# frets-analog.net
KiCad netlist of a schematic drawn in EAGLE
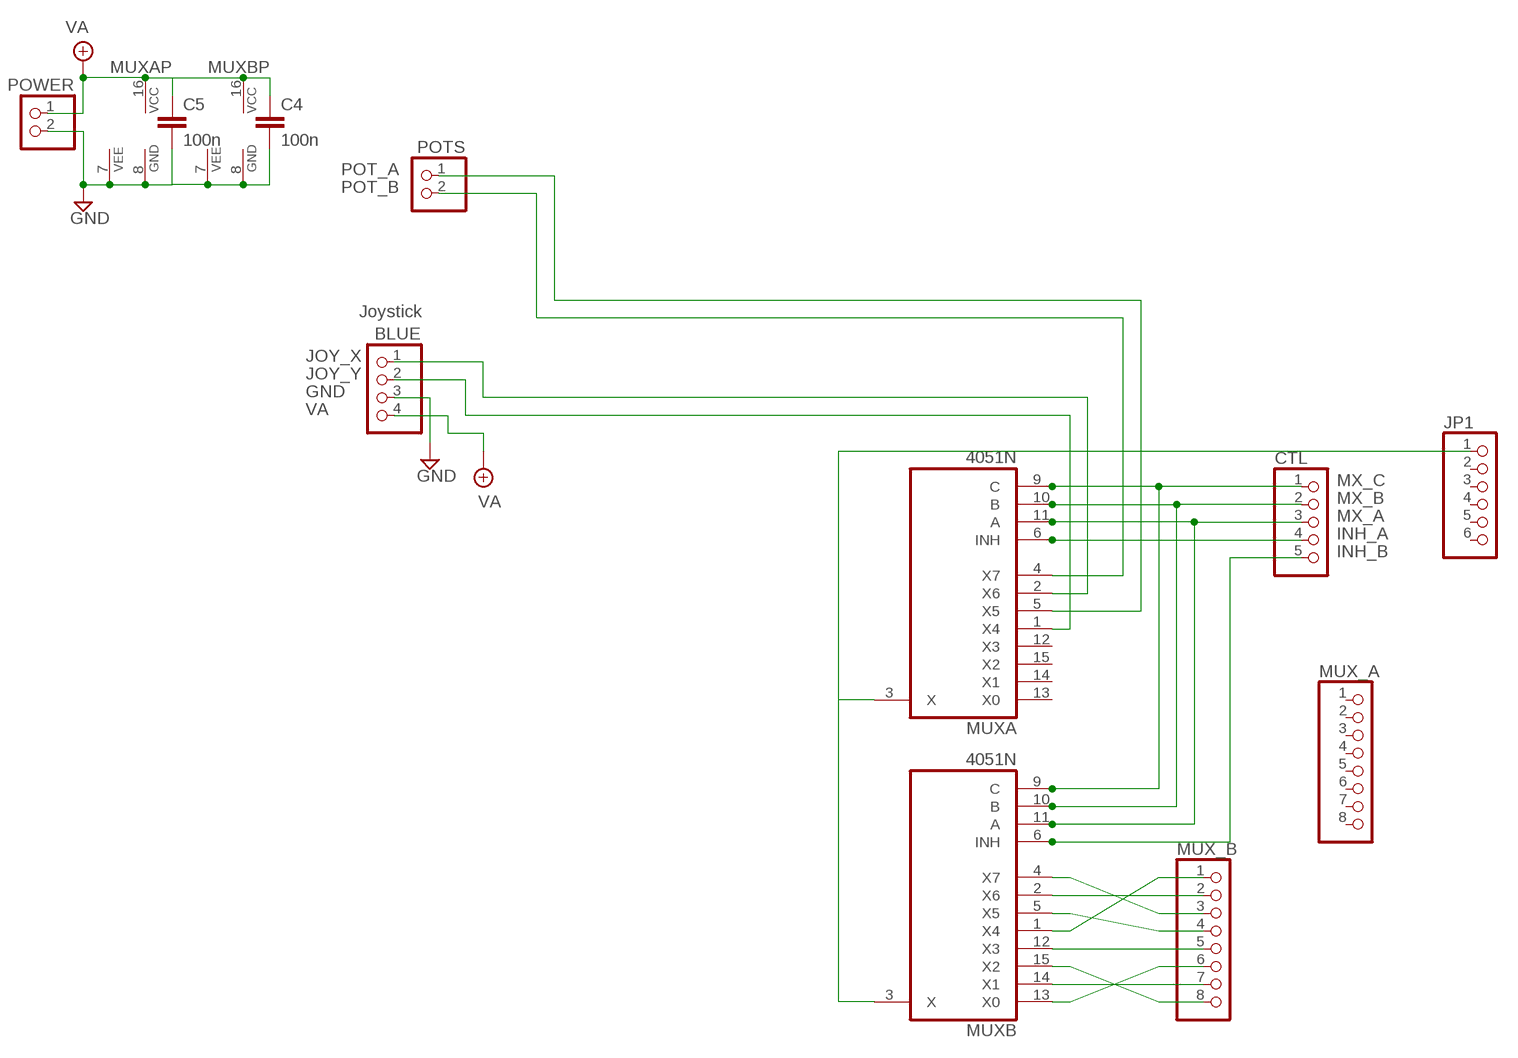
[diagram p0: schematic, sheet 1]

(export (version "E")
  (design (tool "Eeschema 10.0.6"))
  (components
    (comp (ref "BLUE")
      (value "PINHD-1X4")
      (footprint "eagle-import:1X04")
      (libsource (lib "eagle-import") (part "PINHD-1X4"))
    )
    (comp (ref "C4")
      (value "100n")
      (footprint "eagle-import:050X030_050_3")
      (libsource (lib "eagle-import") (part "050X030_050"))
    )
    (comp (ref "C5")
      (value "100n")
      (footprint "eagle-import:050X030_050_3")
      (libsource (lib "eagle-import") (part "050X030_050"))
    )
    (comp (ref "CTL")
      (value "PINHD-1X5")
      (footprint "eagle-import:1X05")
      (libsource (lib "eagle-import") (part "PINHD-1X5"))
    )
    (comp (ref "JP1")
      (value "PINHD-1X6")
      (footprint "eagle-import:1X06")
      (libsource (lib "eagle-import") (part "PINHD-1X6"))
    )
    (comp (ref "MUXA")
      (value "4051N")
      (footprint "eagle-import:DIL16")
      (libsource (lib "eagle-import") (part "4051N"))
    )
    (comp (ref "MUXB")
      (value "4051N")
      (footprint "eagle-import:DIL16")
      (libsource (lib "eagle-import") (part "4051N"))
    )
    (comp (ref "MUX_A")
      (value "PINHD-1X8")
      (footprint "eagle-import:1X08")
      (libsource (lib "eagle-import") (part "PINHD-1X8"))
    )
    (comp (ref "MUX_B")
      (value "PINHD-1X8")
      (footprint "eagle-import:1X08")
      (libsource (lib "eagle-import") (part "PINHD-1X8"))
    )
    (comp (ref "POTS")
      (value "PINHD-1X2")
      (footprint "eagle-import:1X02")
      (libsource (lib "eagle-import") (part "PINHD-1X2"))
    )
    (comp (ref "POWER")
      (value "PINHD-1X2")
      (footprint "eagle-import:1X02")
      (libsource (lib "eagle-import") (part "PINHD-1X2"))
    )
  )
  (nets
    (net (code "1") (name "/INH_A") (class "Default")
      (node (ref "CTL") (pin "4") (pinfunction "4_4") (pintype "passive"))
      (node (ref "MUXA") (pin "6") (pinfunction "INH_6") (pintype "input"))
    )
    (net (code "2") (name "/INH_B") (class "Default")
      (node (ref "CTL") (pin "5") (pinfunction "5_5") (pintype "passive"))
      (node (ref "MUXB") (pin "6") (pinfunction "INH_6") (pintype "input"))
    )
    (net (code "3") (name "/JOY_X") (class "Default")
      (node (ref "BLUE") (pin "1") (pinfunction "1_1") (pintype "passive"))
      (node (ref "MUXA") (pin "2") (pinfunction "X6_2") (pintype "bidirectional"))
    )
    (net (code "4") (name "/JOY_Y") (class "Default")
      (node (ref "BLUE") (pin "2") (pinfunction "2_2") (pintype "passive"))
      (node (ref "MUXA") (pin "1") (pinfunction "X4_1") (pintype "bidirectional"))
    )
    (net (code "5") (name "/MX_A") (class "Default")
      (node (ref "CTL") (pin "3") (pinfunction "3_3") (pintype "passive"))
      (node (ref "MUXA") (pin "11") (pinfunction "A_11") (pintype "input"))
      (node (ref "MUXB") (pin "11") (pinfunction "A_11") (pintype "input"))
    )
    (net (code "6") (name "/MX_B") (class "Default")
      (node (ref "CTL") (pin "2") (pinfunction "2_2") (pintype "passive"))
      (node (ref "MUXA") (pin "10") (pinfunction "B_10") (pintype "input"))
      (node (ref "MUXB") (pin "10") (pinfunction "B_10") (pintype "input"))
    )
    (net (code "7") (name "/MX_C") (class "Default")
      (node (ref "CTL") (pin "1") (pinfunction "1_1") (pintype "passive"))
      (node (ref "MUXA") (pin "9") (pinfunction "C_9") (pintype "input"))
      (node (ref "MUXB") (pin "9") (pinfunction "C_9") (pintype "input"))
    )
    (net (code "8") (name "/POT_A") (class "Default")
      (node (ref "MUXA") (pin "5") (pinfunction "X5_5") (pintype "bidirectional"))
      (node (ref "POTS") (pin "1") (pinfunction "1_1") (pintype "passive"))
    )
    (net (code "9") (name "/POT_B") (class "Default")
      (node (ref "MUXA") (pin "4") (pinfunction "X7_4") (pintype "bidirectional"))
      (node (ref "POTS") (pin "2") (pinfunction "2_2") (pintype "passive"))
    )
    (net (code "10") (name "GND") (class "Default")
      (node (ref "BLUE") (pin "3") (pinfunction "3_3") (pintype "passive"))
      (node (ref "C4") (pin "2") (pinfunction "2_2") (pintype "passive"))
      (node (ref "C5") (pin "2") (pinfunction "2_2") (pintype "passive"))
      (node (ref "MUXA") (pin "7") (pinfunction "VEE_7") (pintype "power_in"))
      (node (ref "MUXA") (pin "8") (pinfunction "GND_8") (pintype "power_in"))
      (node (ref "MUXB") (pin "7") (pinfunction "VEE_7") (pintype "power_in"))
      (node (ref "MUXB") (pin "8") (pinfunction "GND_8") (pintype "power_in"))
      (node (ref "POWER") (pin "2") (pinfunction "2_2") (pintype "passive"))
    )
    (net (code "11") (name "Net-(MUXAA-X)") (class "Default")
      (node (ref "JP1") (pin "1") (pinfunction "1_1") (pintype "passive"))
      (node (ref "MUXA") (pin "3") (pinfunction "X_3") (pintype "bidirectional"))
      (node (ref "MUXB") (pin "3") (pinfunction "X_3") (pintype "bidirectional"))
    )
    (net (code "12") (name "Net-(MUXBA-X0)") (class "Default")
      (node (ref "MUXB") (pin "13") (pinfunction "X0_13") (pintype "bidirectional"))
      (node (ref "MUX_B") (pin "6") (pinfunction "6_6") (pintype "passive"))
    )
    (net (code "13") (name "Net-(MUXBA-X1)") (class "Default")
      (node (ref "MUXB") (pin "14") (pinfunction "X1_14") (pintype "bidirectional"))
      (node (ref "MUX_B") (pin "7") (pinfunction "7_7") (pintype "passive"))
    )
    (net (code "14") (name "Net-(MUXBA-X2)") (class "Default")
      (node (ref "MUXB") (pin "15") (pinfunction "X2_15") (pintype "bidirectional"))
      (node (ref "MUX_B") (pin "8") (pinfunction "8_8") (pintype "passive"))
    )
    (net (code "15") (name "Net-(MUXBA-X3)") (class "Default")
      (node (ref "MUXB") (pin "12") (pinfunction "X3_12") (pintype "bidirectional"))
      (node (ref "MUX_B") (pin "5") (pinfunction "5_5") (pintype "passive"))
    )
    (net (code "16") (name "Net-(MUXBA-X4)") (class "Default")
      (node (ref "MUXB") (pin "1") (pinfunction "X4_1") (pintype "bidirectional"))
      (node (ref "MUX_B") (pin "1") (pinfunction "1_1") (pintype "passive"))
    )
    (net (code "17") (name "Net-(MUXBA-X5)") (class "Default")
      (node (ref "MUXB") (pin "5") (pinfunction "X5_5") (pintype "bidirectional"))
      (node (ref "MUX_B") (pin "4") (pinfunction "4_4") (pintype "passive"))
    )
    (net (code "18") (name "Net-(MUXBA-X6)") (class "Default")
      (node (ref "MUXB") (pin "2") (pinfunction "X6_2") (pintype "bidirectional"))
      (node (ref "MUX_B") (pin "2") (pinfunction "2_2") (pintype "passive"))
    )
    (net (code "19") (name "Net-(MUXBA-X7)") (class "Default")
      (node (ref "MUXB") (pin "4") (pinfunction "X7_4") (pintype "bidirectional"))
      (node (ref "MUX_B") (pin "3") (pinfunction "3_3") (pintype "passive"))
    )
    (net (code "20") (name "VA") (class "Default")
      (node (ref "BLUE") (pin "4") (pinfunction "4_4") (pintype "passive"))
      (node (ref "C4") (pin "1") (pinfunction "1_1") (pintype "passive"))
      (node (ref "C5") (pin "1") (pinfunction "1_1") (pintype "passive"))
      (node (ref "MUXA") (pin "16") (pinfunction "VCC_16") (pintype "power_in"))
      (node (ref "MUXB") (pin "16") (pinfunction "VCC_16") (pintype "power_in"))
      (node (ref "POWER") (pin "1") (pinfunction "1_1") (pintype "passive"))
    )
    (net (code "21") (name "unconnected-(JP1-Pad2)") (class "Default")
      (node (ref "JP1") (pin "2") (pinfunction "2_2") (pintype "passive"))
    )
    (net (code "22") (name "unconnected-(JP1-Pad3)") (class "Default")
      (node (ref "JP1") (pin "3") (pinfunction "3_3") (pintype "passive"))
    )
    (net (code "23") (name "unconnected-(JP1-Pad4)") (class "Default")
      (node (ref "JP1") (pin "4") (pinfunction "4_4") (pintype "passive"))
    )
    (net (code "24") (name "unconnected-(JP1-Pad5)") (class "Default")
      (node (ref "JP1") (pin "5") (pinfunction "5_5") (pintype "passive"))
    )
    (net (code "25") (name "unconnected-(JP1-Pad6)") (class "Default")
      (node (ref "JP1") (pin "6") (pinfunction "6_6") (pintype "passive"))
    )
    (net (code "26") (name "unconnected-(MUXAA-X0-Pad13)") (class "Default")
      (node (ref "MUXA") (pin "13") (pinfunction "X0_13") (pintype "bidirectional"))
    )
    (net (code "27") (name "unconnected-(MUXAA-X1-Pad14)") (class "Default")
      (node (ref "MUXA") (pin "14") (pinfunction "X1_14") (pintype "bidirectional"))
    )
    (net (code "28") (name "unconnected-(MUXAA-X2-Pad15)") (class "Default")
      (node (ref "MUXA") (pin "15") (pinfunction "X2_15") (pintype "bidirectional"))
    )
    (net (code "29") (name "unconnected-(MUXAA-X3-Pad12)") (class "Default")
      (node (ref "MUXA") (pin "12") (pinfunction "X3_12") (pintype "bidirectional"))
    )
    (net (code "30") (name "unconnected-(MUX_A-Pad1)") (class "Default")
      (node (ref "MUX_A") (pin "1") (pinfunction "1_1") (pintype "passive"))
    )
    (net (code "31") (name "unconnected-(MUX_A-Pad2)") (class "Default")
      (node (ref "MUX_A") (pin "2") (pinfunction "2_2") (pintype "passive"))
    )
    (net (code "32") (name "unconnected-(MUX_A-Pad3)") (class "Default")
      (node (ref "MUX_A") (pin "3") (pinfunction "3_3") (pintype "passive"))
    )
    (net (code "33") (name "unconnected-(MUX_A-Pad4)") (class "Default")
      (node (ref "MUX_A") (pin "4") (pinfunction "4_4") (pintype "passive"))
    )
    (net (code "34") (name "unconnected-(MUX_A-Pad5)") (class "Default")
      (node (ref "MUX_A") (pin "5") (pinfunction "5_5") (pintype "passive"))
    )
    (net (code "35") (name "unconnected-(MUX_A-Pad6)") (class "Default")
      (node (ref "MUX_A") (pin "6") (pinfunction "6_6") (pintype "passive"))
    )
    (net (code "36") (name "unconnected-(MUX_A-Pad7)") (class "Default")
      (node (ref "MUX_A") (pin "7") (pinfunction "7_7") (pintype "passive"))
    )
    (net (code "37") (name "unconnected-(MUX_A-Pad8)") (class "Default")
      (node (ref "MUX_A") (pin "8") (pinfunction "8_8") (pintype "passive"))
    )
  )
)
